# kopping_c.net
KiCad netlist of a schematic drawn in EAGLE
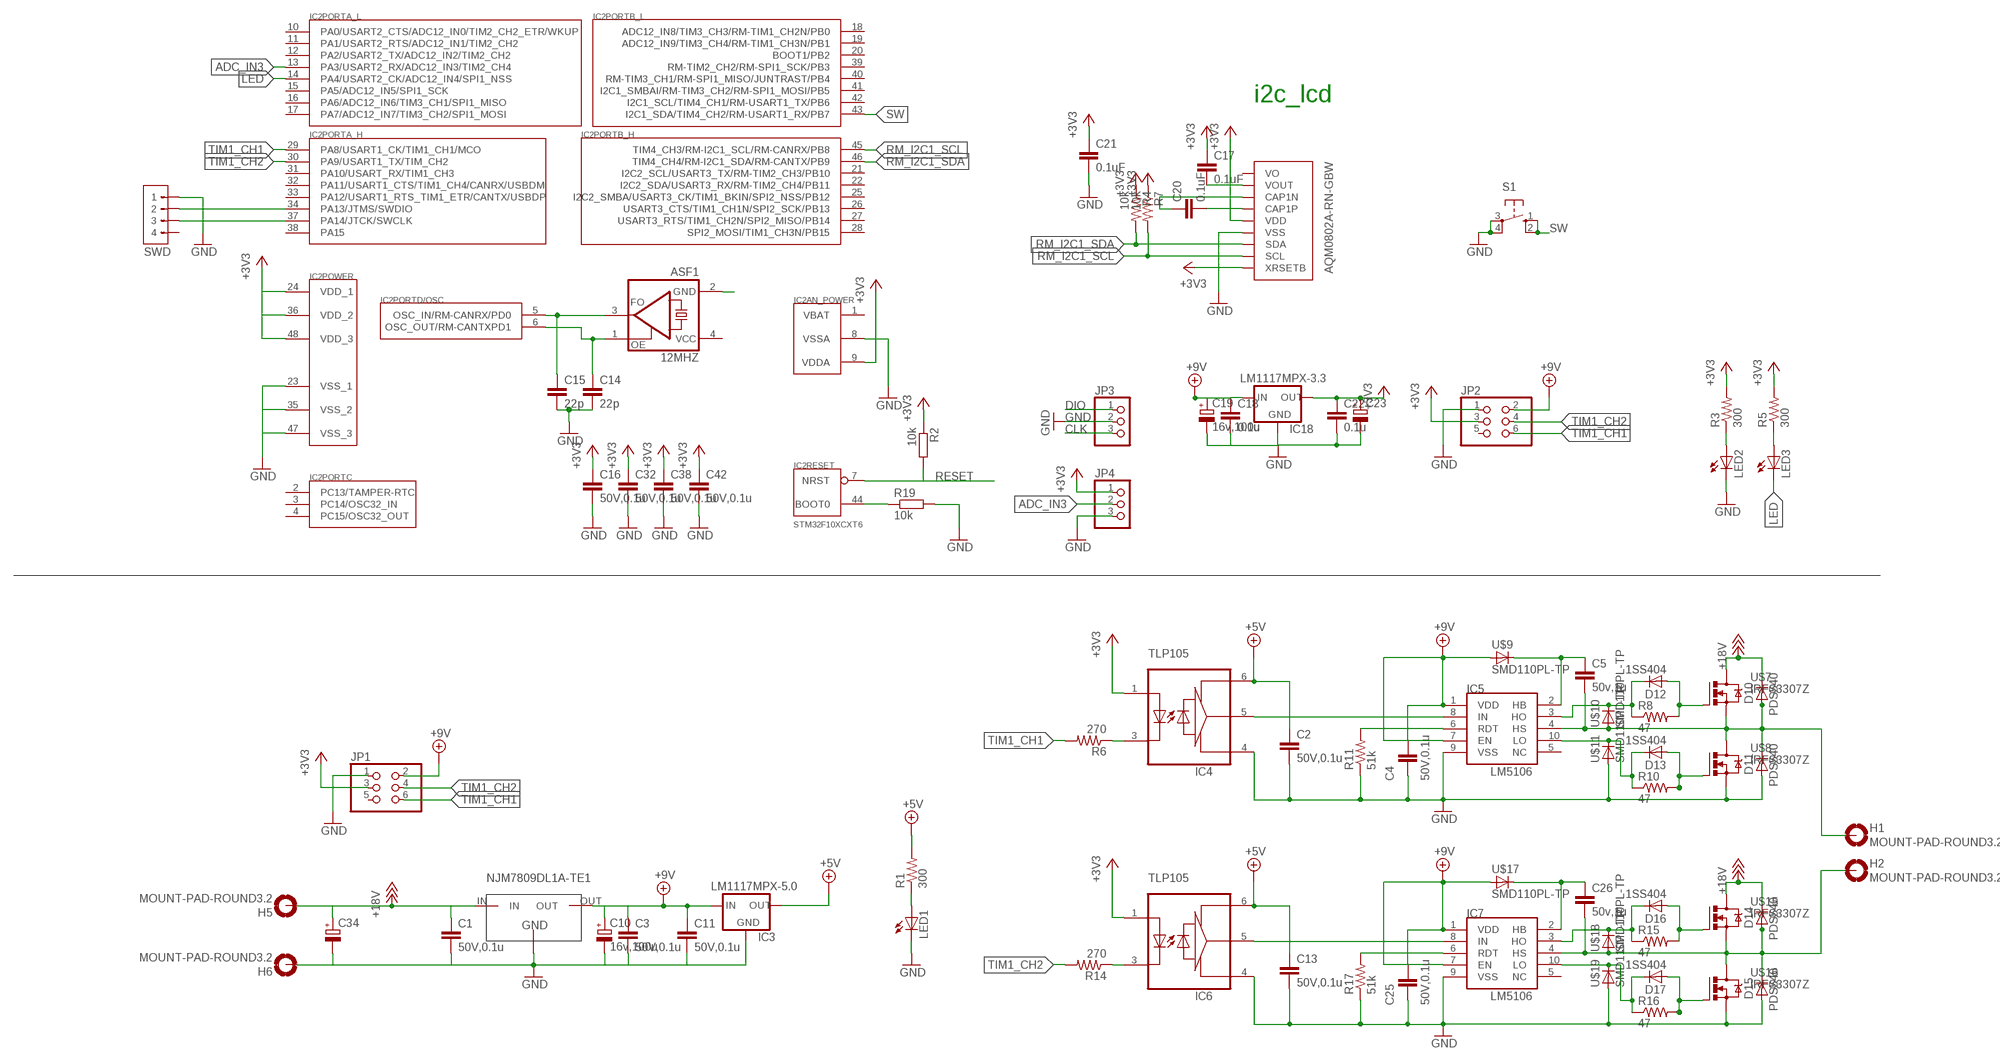
[diagram p0: schematic, sheet 1]

(export (version "E")
  (design (tool "Eeschema 10.0.6"))
  (components
    (comp (ref "12MHZ")
      (value "ASF1")
      (footprint "eagle-import:ASF")
      (libsource (lib "eagle-import") (part "ASF1"))
    )
    (comp (ref "AQM0802A-RN-GBW")
      (value "AQM0802A-RN-GBW")
      (footprint "eagle-import:AQM0802")
      (libsource (lib "eagle-import") (part "AQM0802A-RN-GBW"))
    )
    (comp (ref "C1")
      (value "50V,0.1u")
      (footprint "eagle-import:C0603")
      (libsource (lib "eagle-import") (part "C-EUC0603"))
    )
    (comp (ref "C2")
      (value "50V,0.1u")
      (footprint "eagle-import:C0603")
      (libsource (lib "eagle-import") (part "C-EUC0603"))
    )
    (comp (ref "C3")
      (value "50V,0.1u")
      (footprint "eagle-import:C0603")
      (libsource (lib "eagle-import") (part "C-EUC0603"))
    )
    (comp (ref "C4")
      (value "50V,0.1u")
      (footprint "eagle-import:C0603")
      (libsource (lib "eagle-import") (part "C-EUC0603"))
    )
    (comp (ref "C5")
      (value "50v,1u")
      (footprint "eagle-import:C0603")
      (libsource (lib "eagle-import") (part "C-EUC0603"))
    )
    (comp (ref "C10")
      (value "16v,100u")
      (footprint "eagle-import:153CLV-0605")
      (libsource (lib "eagle-import") (part "CPOL-EU153CLV-0605"))
    )
    (comp (ref "C11")
      (value "50V,0.1u")
      (footprint "eagle-import:C0603")
      (libsource (lib "eagle-import") (part "C-EUC0603"))
    )
    (comp (ref "C13")
      (value "50V,0.1u")
      (footprint "eagle-import:C0603")
      (libsource (lib "eagle-import") (part "C-EUC0603"))
    )
    (comp (ref "C14")
      (value "22p")
      (footprint "eagle-import:C0603")
      (libsource (lib "eagle-import") (part "C-EUC0603"))
    )
    (comp (ref "C15")
      (value "22p")
      (footprint "eagle-import:C0603")
      (libsource (lib "eagle-import") (part "C-EUC0603"))
    )
    (comp (ref "C16")
      (value "50V,0.1u")
      (footprint "eagle-import:C0603K")
      (libsource (lib "eagle-import") (part "resistor_C-EUC0603K"))
    )
    (comp (ref "C17")
      (value "0.1uF")
      (footprint "eagle-import:C0603")
      (libsource (lib "eagle-import") (part "resistor_C-EUC0603"))
    )
    (comp (ref "C18")
      (value "0.1u")
      (footprint "eagle-import:C0603")
      (libsource (lib "eagle-import") (part "C-EUC0603"))
    )
    (comp (ref "C19")
      (value "16v,100u")
      (footprint "eagle-import:153CLV-0605")
      (libsource (lib "eagle-import") (part "CPOL-EU153CLV-0605"))
    )
    (comp (ref "C20")
      (value "0.1uF")
      (footprint "eagle-import:C0603")
      (libsource (lib "eagle-import") (part "resistor_C-EUC0603"))
    )
    (comp (ref "C21")
      (value "0.1uF")
      (footprint "eagle-import:C0603")
      (libsource (lib "eagle-import") (part "resistor_C-EUC0603"))
    )
    (comp (ref "C22")
      (value "0.1u")
      (footprint "eagle-import:C0603K")
      (libsource (lib "eagle-import") (part "resistor_C-EUC0603K"))
    )
    (comp (ref "C23")
      (value "CPOL-EU153CLV-0505")
      (footprint "eagle-import:153CLV-0505")
      (libsource (lib "eagle-import") (part "CPOL-EU153CLV-0505"))
    )
    (comp (ref "C25")
      (value "50V,0.1u")
      (footprint "eagle-import:C0603")
      (libsource (lib "eagle-import") (part "C-EUC0603"))
    )
    (comp (ref "C26")
      (value "50v,1u")
      (footprint "eagle-import:C0603")
      (libsource (lib "eagle-import") (part "C-EUC0603"))
    )
    (comp (ref "C32")
      (value "50V,0.1u")
      (footprint "eagle-import:C0603K")
      (libsource (lib "eagle-import") (part "resistor_C-EUC0603K"))
    )
    (comp (ref "C34")
      (value "CPOL-EUE7.5-16")
      (footprint "eagle-import:E7,5-16")
      (libsource (lib "eagle-import") (part "CPOL-EUE7.5-16"))
    )
    (comp (ref "C38")
      (value "50V,0.1u")
      (footprint "eagle-import:C0603K")
      (libsource (lib "eagle-import") (part "resistor_C-EUC0603K"))
    )
    (comp (ref "C42")
      (value "50V,0.1u")
      (footprint "eagle-import:C0603K")
      (libsource (lib "eagle-import") (part "resistor_C-EUC0603K"))
    )
    (comp (ref "D10")
      (value "PDS540")
      (footprint "eagle-import:POWER_DI_5")
      (libsource (lib "eagle-import") (part "PDS540"))
    )
    (comp (ref "D11")
      (value "PDS540")
      (footprint "eagle-import:POWER_DI_5")
      (libsource (lib "eagle-import") (part "PDS540"))
    )
    (comp (ref "D12")
      (value "1SS404")
      (footprint "eagle-import:USC(1.25X2.5)")
      (libsource (lib "eagle-import") (part "1SS404"))
    )
    (comp (ref "D13")
      (value "1SS404")
      (footprint "eagle-import:USC(1.25X2.5)")
      (libsource (lib "eagle-import") (part "1SS404"))
    )
    (comp (ref "D14")
      (value "PDS540")
      (footprint "eagle-import:POWER_DI_5")
      (libsource (lib "eagle-import") (part "PDS540"))
    )
    (comp (ref "D15")
      (value "PDS540")
      (footprint "eagle-import:POWER_DI_5")
      (libsource (lib "eagle-import") (part "PDS540"))
    )
    (comp (ref "D16")
      (value "1SS404")
      (footprint "eagle-import:USC(1.25X2.5)")
      (libsource (lib "eagle-import") (part "1SS404"))
    )
    (comp (ref "D17")
      (value "1SS404")
      (footprint "eagle-import:USC(1.25X2.5)")
      (libsource (lib "eagle-import") (part "1SS404"))
    )
    (comp (ref "H1")
      (value "MOUNT-PAD-ROUND3.2")
      (footprint "eagle-import:3,2-PAD")
      (libsource (lib "eagle-import") (part "MOUNT-PAD-ROUND3.2"))
    )
    (comp (ref "H2")
      (value "MOUNT-PAD-ROUND3.2")
      (footprint "eagle-import:3,2-PAD")
      (libsource (lib "eagle-import") (part "MOUNT-PAD-ROUND3.2"))
    )
    (comp (ref "H5")
      (value "MOUNT-PAD-ROUND3.2")
      (footprint "eagle-import:3,2-PAD")
      (libsource (lib "eagle-import") (part "MOUNT-PAD-ROUND3.2"))
    )
    (comp (ref "H6")
      (value "MOUNT-PAD-ROUND3.2")
      (footprint "eagle-import:3,2-PAD")
      (libsource (lib "eagle-import") (part "MOUNT-PAD-ROUND3.2"))
    )
    (comp (ref "IC2")
      (value "STM32F10XCXT6")
      (footprint "eagle-import:TQFP48")
      (libsource (lib "eagle-import") (part "STM32F10XCXT6"))
    )
    (comp (ref "IC3")
      (value "LM1117MPX-5.0")
      (footprint "eagle-import:SOT223")
      (libsource (lib "eagle-import") (part "LM1117"))
    )
    (comp (ref "IC4")
      (value "TLP105")
      (footprint "eagle-import:MFSOP6")
      (libsource (lib "eagle-import") (part "TLP117"))
    )
    (comp (ref "IC5")
      (value "LM5106")
      (footprint "eagle-import:MSOP10")
      (libsource (lib "eagle-import") (part "LM5106"))
    )
    (comp (ref "IC6")
      (value "TLP105")
      (footprint "eagle-import:MFSOP6")
      (libsource (lib "eagle-import") (part "TLP117"))
    )
    (comp (ref "IC7")
      (value "LM5106")
      (footprint "eagle-import:MSOP10")
      (libsource (lib "eagle-import") (part "LM5106"))
    )
    (comp (ref "IC18")
      (value "LM1117MPX-3.3")
      (footprint "eagle-import:SOT223")
      (libsource (lib "eagle-import") (part "LM1117"))
    )
    (comp (ref "JP1")
      (value "PINHD-2X3")
      (footprint "eagle-import:2X03")
      (libsource (lib "eagle-import") (part "PINHD-2X3"))
    )
    (comp (ref "JP2")
      (value "PINHD-2X3")
      (footprint "eagle-import:2X03")
      (libsource (lib "eagle-import") (part "PINHD-2X3"))
    )
    (comp (ref "JP3")
      (value "PINHD-1X3/90")
      (footprint "eagle-import:1X03_90")
      (libsource (lib "eagle-import") (part "PINHD-1X3/90"))
    )
    (comp (ref "JP4")
      (value "PINHD-1X3/90")
      (footprint "eagle-import:1X03_90")
      (libsource (lib "eagle-import") (part "PINHD-1X3/90"))
    )
    (comp (ref "LED1")
      (value "LEDCHIPLED_1206")
      (footprint "eagle-import:CHIPLED_1206")
      (libsource (lib "eagle-import") (part "LEDCHIPLED_1206"))
    )
    (comp (ref "LED2")
      (value "LEDCHIPLED_1206")
      (footprint "eagle-import:CHIPLED_1206")
      (libsource (lib "eagle-import") (part "LEDCHIPLED_1206"))
    )
    (comp (ref "LED3")
      (value "LEDCHIPLED_1206")
      (footprint "eagle-import:CHIPLED_1206")
      (libsource (lib "eagle-import") (part "LEDCHIPLED_1206"))
    )
    (comp (ref "R1")
      (value "300")
      (footprint "eagle-import:M2012")
      (libsource (lib "eagle-import") (part "R-US_M2012"))
    )
    (comp (ref "R2")
      (value "10k")
      (footprint "eagle-import:R0603")
      (libsource (lib "eagle-import") (part "R-EU_R0603"))
    )
    (comp (ref "R3")
      (value "300")
      (footprint "eagle-import:M2012")
      (libsource (lib "eagle-import") (part "R-US_M2012"))
    )
    (comp (ref "R4")
      (value "10k")
      (footprint "eagle-import:R0603")
      (libsource (lib "eagle-import") (part "resistor_R-US_R0603"))
    )
    (comp (ref "R5")
      (value "300")
      (footprint "eagle-import:M2012")
      (libsource (lib "eagle-import") (part "R-US_M2012"))
    )
    (comp (ref "R6")
      (value "270")
      (footprint "eagle-import:R0603")
      (libsource (lib "eagle-import") (part "resistor_R-US_R0603"))
    )
    (comp (ref "R7")
      (value "10k")
      (footprint "eagle-import:R0603")
      (libsource (lib "eagle-import") (part "resistor_R-US_R0603"))
    )
    (comp (ref "R8")
      (value "47")
      (footprint "eagle-import:R0603")
      (libsource (lib "eagle-import") (part "resistor_R-US_R0603"))
    )
    (comp (ref "R10")
      (value "47")
      (footprint "eagle-import:R0603")
      (libsource (lib "eagle-import") (part "resistor_R-US_R0603"))
    )
    (comp (ref "R11")
      (value "51k")
      (footprint "eagle-import:R0603")
      (libsource (lib "eagle-import") (part "R-US_R0603"))
    )
    (comp (ref "R14")
      (value "270")
      (footprint "eagle-import:R0603")
      (libsource (lib "eagle-import") (part "resistor_R-US_R0603"))
    )
    (comp (ref "R15")
      (value "47")
      (footprint "eagle-import:R0603")
      (libsource (lib "eagle-import") (part "resistor_R-US_R0603"))
    )
    (comp (ref "R16")
      (value "47")
      (footprint "eagle-import:R0603")
      (libsource (lib "eagle-import") (part "resistor_R-US_R0603"))
    )
    (comp (ref "R17")
      (value "51k")
      (footprint "eagle-import:R0603")
      (libsource (lib "eagle-import") (part "R-US_R0603"))
    )
    (comp (ref "R19")
      (value "10k")
      (footprint "eagle-import:R0603")
      (libsource (lib "eagle-import") (part "R-EU_R0603"))
    )
    (comp (ref "S1")
      (value "10-XX")
      (footprint "eagle-import:B3F-10XX")
      (fields (field (name "MPN") "B3F-1000"))
      (libsource (lib "eagle-import") (part "10-XX"))
    )
    (comp (ref "SWD")
      (value "TOP_TYPE_4PIN")
      (footprint "eagle-import:TOP_TYPE_4PIN")
      (libsource (lib "eagle-import") (part "TOP_TYPE_4PIN"))
    )
    (comp (ref "U$3")
      (value "TO252")
      (footprint "eagle-import:TO252")
      (libsource (lib "eagle-import") (part "TO252"))
    )
    (comp (ref "U$7")
      (value "IRFS3307Z")
      (footprint "eagle-import:IRFS3307Z")
      (libsource (lib "eagle-import") (part "IRFS3307Z"))
    )
    (comp (ref "U$8")
      (value "IRFS3307Z")
      (footprint "eagle-import:IRFS3307Z")
      (libsource (lib "eagle-import") (part "IRFS3307Z"))
    )
    (comp (ref "U$9")
      (value "SMD110PL-TP")
      (footprint "eagle-import:SOD123")
      (libsource (lib "eagle-import") (part "SMD110PL-TP"))
    )
    (comp (ref "U$10")
      (value "SMD110PL-TP")
      (footprint "eagle-import:SOD123")
      (libsource (lib "eagle-import") (part "SMD110PL-TP"))
    )
    (comp (ref "U$11")
      (value "SMD110PL-TP")
      (footprint "eagle-import:SOD123")
      (libsource (lib "eagle-import") (part "SMD110PL-TP"))
    )
    (comp (ref "U$15")
      (value "IRFS3307Z")
      (footprint "eagle-import:IRFS3307Z")
      (libsource (lib "eagle-import") (part "IRFS3307Z"))
    )
    (comp (ref "U$16")
      (value "IRFS3307Z")
      (footprint "eagle-import:IRFS3307Z")
      (libsource (lib "eagle-import") (part "IRFS3307Z"))
    )
    (comp (ref "U$17")
      (value "SMD110PL-TP")
      (footprint "eagle-import:SOD123")
      (libsource (lib "eagle-import") (part "SMD110PL-TP"))
    )
    (comp (ref "U$18")
      (value "SMD110PL-TP")
      (footprint "eagle-import:SOD123")
      (libsource (lib "eagle-import") (part "SMD110PL-TP"))
    )
    (comp (ref "U$19")
      (value "SMD110PL-TP")
      (footprint "eagle-import:SOD123")
      (libsource (lib "eagle-import") (part "SMD110PL-TP"))
    )
  )
  (nets
    (net (code "1") (name "+3V3") (class "Default")
      (node (ref "AQM0802A-RN-GBW") (pin "P$5") (pinfunction "VDD_P$5") (pintype "bidirectional"))
      (node (ref "AQM0802A-RN-GBW") (pin "P$9") (pinfunction "XRSETB_P$9") (pintype "bidirectional"))
      (node (ref "C16") (pin "1") (pinfunction "1_1") (pintype "passive"))
      (node (ref "C17") (pin "1") (pinfunction "1_1") (pintype "passive"))
      (node (ref "C21") (pin "1") (pinfunction "1_1") (pintype "passive"))
      (node (ref "C22") (pin "1") (pinfunction "1_1") (pintype "passive"))
      (node (ref "C23") (pin "+") (pinfunction "+_+") (pintype "passive"))
      (node (ref "C32") (pin "1") (pinfunction "1_1") (pintype "passive"))
      (node (ref "C38") (pin "1") (pinfunction "1_1") (pintype "passive"))
      (node (ref "C42") (pin "1") (pinfunction "1_1") (pintype "passive"))
      (node (ref "IC18") (pin "2") (pinfunction "OUT1_2") (pintype "passive"))
      (node (ref "IC18") (pin "4") (pinfunction "OUT_4") (pintype "passive"))
      (node (ref "IC2") (pin "24") (pinfunction "VDD_1_24") (pintype "power_in"))
      (node (ref "IC2") (pin "36") (pinfunction "VDD_2_36") (pintype "power_in"))
      (node (ref "IC2") (pin "48") (pinfunction "VDD_3_48") (pintype "power_in"))
      (node (ref "IC2") (pin "9") (pinfunction "VDDA_9") (pintype "power_in"))
      (node (ref "IC4") (pin "1") (pinfunction "1_1") (pintype "input"))
      (node (ref "IC6") (pin "1") (pinfunction "1_1") (pintype "input"))
      (node (ref "JP1") (pin "3") (pinfunction "3_3") (pintype "passive"))
      (node (ref "JP2") (pin "3") (pinfunction "3_3") (pintype "passive"))
      (node (ref "JP4") (pin "1") (pinfunction "1_1") (pintype "passive"))
      (node (ref "R2") (pin "1") (pinfunction "1_1") (pintype "passive"))
      (node (ref "R3") (pin "2") (pinfunction "2_2") (pintype "passive"))
      (node (ref "R4") (pin "1") (pinfunction "1_1") (pintype "passive"))
      (node (ref "R5") (pin "2") (pinfunction "2_2") (pintype "passive"))
      (node (ref "R7") (pin "1") (pinfunction "1_1") (pintype "passive"))
    )
    (net (code "2") (name "+5V") (class "Default")
      (node (ref "C13") (pin "1") (pinfunction "1_1") (pintype "passive"))
      (node (ref "C2") (pin "1") (pinfunction "1_1") (pintype "passive"))
      (node (ref "IC3") (pin "2") (pinfunction "OUT1_2") (pintype "passive"))
      (node (ref "IC3") (pin "4") (pinfunction "OUT_4") (pintype "passive"))
      (node (ref "IC4") (pin "6") (pinfunction "VCC_6") (pintype "power_in"))
      (node (ref "IC6") (pin "6") (pinfunction "VCC_6") (pintype "power_in"))
      (node (ref "R1") (pin "2") (pinfunction "2_2") (pintype "passive"))
    )
    (net (code "3") (name "+9V") (class "Default")
      (node (ref "C10") (pin "+") (pinfunction "+_+") (pintype "passive"))
      (node (ref "C11") (pin "1") (pinfunction "1_1") (pintype "passive"))
      (node (ref "C18") (pin "1") (pinfunction "1_1") (pintype "passive"))
      (node (ref "C19") (pin "+") (pinfunction "+_+") (pintype "passive"))
      (node (ref "C25") (pin "1") (pinfunction "1_1") (pintype "passive"))
      (node (ref "C3") (pin "1") (pinfunction "1_1") (pintype "passive"))
      (node (ref "C4") (pin "1") (pinfunction "1_1") (pintype "passive"))
      (node (ref "IC18") (pin "3") (pinfunction "IN_3") (pintype "input"))
      (node (ref "IC3") (pin "3") (pinfunction "IN_3") (pintype "input"))
      (node (ref "IC5") (pin "1") (pinfunction "VDD_1") (pintype "power_in"))
      (node (ref "IC5") (pin "7") (pinfunction "EN_7") (pintype "input"))
      (node (ref "IC7") (pin "1") (pinfunction "VDD_1") (pintype "power_in"))
      (node (ref "IC7") (pin "7") (pinfunction "EN_7") (pintype "input"))
      (node (ref "JP1") (pin "2") (pinfunction "2_2") (pintype "passive"))
      (node (ref "JP2") (pin "2") (pinfunction "2_2") (pintype "passive"))
      (node (ref "U$17") (pin "A") (pinfunction "A_A") (pintype "passive"))
      (node (ref "U$3") (pin "OUT") (pinfunction "OUT_OUT") (pintype "bidirectional"))
      (node (ref "U$9") (pin "A") (pinfunction "A_A") (pintype "passive"))
    )
    (net (code "4") (name "+18V") (class "Default")
      (node (ref "C1") (pin "1") (pinfunction "1_1") (pintype "passive"))
      (node (ref "C34") (pin "+") (pinfunction "+_+") (pintype "passive"))
      (node (ref "D10") (pin "K") (pinfunction "C_K") (pintype "passive"))
      (node (ref "D14") (pin "K") (pinfunction "C_K") (pintype "passive"))
      (node (ref "H5") (pin "B3,2") (pinfunction "MOUNT_B3,2") (pintype "passive"))
      (node (ref "U$15") (pin "2") (pinfunction "D1_2") (pintype "passive"))
      (node (ref "U$3") (pin "IN") (pinfunction "IN_IN") (pintype "bidirectional"))
      (node (ref "U$7") (pin "2") (pinfunction "D1_2") (pintype "passive"))
    )
    (net (code "5") (name "/CLK") (class "Default")
      (node (ref "IC2") (pin "37") (pinfunction "PA14/JTCK/SWCLK_37") (pintype "bidirectional"))
      (node (ref "JP3") (pin "3") (pinfunction "3_3") (pintype "passive"))
      (node (ref "SWD") (pin "3") (pinfunction "3_3") (pintype "passive"))
    )
    (net (code "6") (name "/DIO") (class "Default")
      (node (ref "IC2") (pin "34") (pinfunction "PA13/JTMS/SWDIO_34") (pintype "bidirectional"))
      (node (ref "JP3") (pin "1") (pinfunction "1_1") (pintype "passive"))
      (node (ref "SWD") (pin "2") (pinfunction "2_2") (pintype "passive"))
    )
    (net (code "7") (name "/RESET") (class "Default")
      (node (ref "IC2") (pin "7") (pinfunction "NRST_7") (pintype "input"))
      (node (ref "R2") (pin "2") (pinfunction "2_2") (pintype "passive"))
    )
    (net (code "8") (name "/VBAT") (class "Default")
      (node (ref "IC2") (pin "1") (pinfunction "VBAT_1") (pintype "power_in"))
    )
    (net (code "9") (name "/VCC") (class "Default")
      (node (ref "12MHZ") (pin "4") (pinfunction "VCC_4") (pintype "power_in"))
    )
    (net (code "10") (name "ADC_IN3") (class "Default")
      (node (ref "IC2") (pin "13") (pinfunction "PA3/USART2_RX/ADC12_IN3/TIM2_CH4_13") (pintype "bidirectional"))
      (node (ref "JP4") (pin "2") (pinfunction "2_2") (pintype "passive"))
    )
    (net (code "11") (name "GND") (class "Default")
      (node (ref "AQM0802A-RN-GBW") (pin "P$6") (pinfunction "VSS_P$6") (pintype "bidirectional"))
      (node (ref "C1") (pin "2") (pinfunction "2_2") (pintype "passive"))
      (node (ref "C10") (pin "-") (pinfunction "-_-") (pintype "passive"))
      (node (ref "C11") (pin "2") (pinfunction "2_2") (pintype "passive"))
      (node (ref "C13") (pin "2") (pinfunction "2_2") (pintype "passive"))
      (node (ref "C14") (pin "2") (pinfunction "2_2") (pintype "passive"))
      (node (ref "C15") (pin "2") (pinfunction "2_2") (pintype "passive"))
      (node (ref "C16") (pin "2") (pinfunction "2_2") (pintype "passive"))
      (node (ref "C18") (pin "2") (pinfunction "2_2") (pintype "passive"))
      (node (ref "C19") (pin "-") (pinfunction "-_-") (pintype "passive"))
      (node (ref "C2") (pin "2") (pinfunction "2_2") (pintype "passive"))
      (node (ref "C21") (pin "2") (pinfunction "2_2") (pintype "passive"))
      (node (ref "C22") (pin "2") (pinfunction "2_2") (pintype "passive"))
      (node (ref "C23") (pin "-") (pinfunction "-_-") (pintype "passive"))
      (node (ref "C25") (pin "2") (pinfunction "2_2") (pintype "passive"))
      (node (ref "C3") (pin "2") (pinfunction "2_2") (pintype "passive"))
      (node (ref "C32") (pin "2") (pinfunction "2_2") (pintype "passive"))
      (node (ref "C34") (pin "-") (pinfunction "-_-") (pintype "passive"))
      (node (ref "C38") (pin "2") (pinfunction "2_2") (pintype "passive"))
      (node (ref "C4") (pin "2") (pinfunction "2_2") (pintype "passive"))
      (node (ref "C42") (pin "2") (pinfunction "2_2") (pintype "passive"))
      (node (ref "D11") (pin "A1") (pinfunction "A1_A1") (pintype "passive"))
      (node (ref "D11") (pin "A2") (pinfunction "A_A2") (pintype "passive"))
      (node (ref "D15") (pin "A1") (pinfunction "A1_A1") (pintype "passive"))
      (node (ref "D15") (pin "A2") (pinfunction "A_A2") (pintype "passive"))
      (node (ref "H6") (pin "B3,2") (pinfunction "MOUNT_B3,2") (pintype "passive"))
      (node (ref "IC18") (pin "1") (pinfunction "GND_1") (pintype "input"))
      (node (ref "IC2") (pin "23") (pinfunction "VSS_1_23") (pintype "power_in"))
      (node (ref "IC2") (pin "35") (pinfunction "VSS_2_35") (pintype "power_in"))
      (node (ref "IC2") (pin "47") (pinfunction "VSS_3_47") (pintype "power_in"))
      (node (ref "IC2") (pin "8") (pinfunction "VSSA_8") (pintype "power_in"))
      (node (ref "IC3") (pin "1") (pinfunction "GND_1") (pintype "input"))
      (node (ref "IC4") (pin "4") (pinfunction "GND_4") (pintype "power_in"))
      (node (ref "IC5") (pin "9") (pinfunction "VSS_9") (pintype "power_in"))
      (node (ref "IC6") (pin "4") (pinfunction "GND_4") (pintype "power_in"))
      (node (ref "IC7") (pin "9") (pinfunction "VSS_9") (pintype "power_in"))
      (node (ref "JP1") (pin "1") (pinfunction "1_1") (pintype "passive"))
      (node (ref "JP2") (pin "1") (pinfunction "1_1") (pintype "passive"))
      (node (ref "JP3") (pin "2") (pinfunction "2_2") (pintype "passive"))
      (node (ref "JP4") (pin "3") (pinfunction "3_3") (pintype "passive"))
      (node (ref "LED1") (pin "C") (pinfunction "C_C") (pintype "passive"))
      (node (ref "LED2") (pin "C") (pinfunction "C_C") (pintype "passive"))
      (node (ref "R11") (pin "1") (pinfunction "1_1") (pintype "passive"))
      (node (ref "R17") (pin "1") (pinfunction "1_1") (pintype "passive"))
      (node (ref "R19") (pin "2") (pinfunction "2_2") (pintype "passive"))
      (node (ref "S1") (pin "3") (pinfunction "P_3") (pintype "passive"))
      (node (ref "S1") (pin "4") (pinfunction "P1_4") (pintype "passive"))
      (node (ref "SWD") (pin "1") (pinfunction "1_1") (pintype "passive"))
      (node (ref "U$11") (pin "A") (pinfunction "A_A") (pintype "passive"))
      (node (ref "U$16") (pin "3") (pinfunction "S_3") (pintype "passive"))
      (node (ref "U$19") (pin "A") (pinfunction "A_A") (pintype "passive"))
      (node (ref "U$3") (pin "GND") (pinfunction "GND_GND") (pintype "bidirectional"))
      (node (ref "U$8") (pin "3") (pinfunction "S_3") (pintype "passive"))
    )
    (net (code "12") (name "LED") (class "Default")
      (node (ref "IC2") (pin "14") (pinfunction "PA4/USART2_CK/ADC12_IN4/SPI1_NSS_14") (pintype "bidirectional"))
      (node (ref "LED3") (pin "C") (pinfunction "C_C") (pintype "passive"))
    )
    (net (code "13") (name "Net-(12MHZ-FO)") (class "Default")
      (node (ref "12MHZ") (pin "3") (pinfunction "FO_3") (pintype "output"))
      (node (ref "C15") (pin "1") (pinfunction "1_1") (pintype "passive"))
      (node (ref "IC2") (pin "5") (pinfunction "OSC_IN/RM-CANRX/PD0_5") (pintype "bidirectional"))
    )
    (net (code "14") (name "Net-(12MHZ-OE)") (class "Default")
      (node (ref "12MHZ") (pin "1") (pinfunction "OE_1") (pintype "input"))
      (node (ref "C14") (pin "1") (pinfunction "1_1") (pintype "passive"))
      (node (ref "IC2") (pin "6") (pinfunction "OSC_OUT/RM-CANTXPD1_6") (pintype "bidirectional"))
    )
    (net (code "15") (name "Net-(AQM0802A-RN-GBW-CAP1N)") (class "Default")
      (node (ref "AQM0802A-RN-GBW") (pin "P$3") (pinfunction "CAP1N_P$3") (pintype "bidirectional"))
      (node (ref "C20") (pin "1") (pinfunction "1_1") (pintype "passive"))
    )
    (net (code "16") (name "Net-(AQM0802A-RN-GBW-CAP1P)") (class "Default")
      (node (ref "AQM0802A-RN-GBW") (pin "P$4") (pinfunction "CAP1P_P$4") (pintype "bidirectional"))
      (node (ref "C20") (pin "2") (pinfunction "2_2") (pintype "passive"))
    )
    (net (code "17") (name "Net-(AQM0802A-RN-GBW-VOUT)") (class "Default")
      (node (ref "AQM0802A-RN-GBW") (pin "P$2") (pinfunction "VOUT_P$2") (pintype "bidirectional"))
      (node (ref "C17") (pin "2") (pinfunction "2_2") (pintype "passive"))
    )
    (net (code "18") (name "Net-(D10-A)") (class "Default")
      (node (ref "C5") (pin "2") (pinfunction "2_2") (pintype "passive"))
      (node (ref "D10") (pin "A1") (pinfunction "A1_A1") (pintype "passive"))
      (node (ref "D10") (pin "A2") (pinfunction "A_A2") (pintype "passive"))
      (node (ref "D11") (pin "K") (pinfunction "C_K") (pintype "passive"))
      (node (ref "H1") (pin "B3,2") (pinfunction "MOUNT_B3,2") (pintype "passive"))
      (node (ref "IC5") (pin "4") (pinfunction "HS_4") (pintype "passive"))
      (node (ref "U$10") (pin "A") (pinfunction "A_A") (pintype "passive"))
      (node (ref "U$7") (pin "3") (pinfunction "S_3") (pintype "passive"))
      (node (ref "U$8") (pin "2") (pinfunction "D1_2") (pintype "passive"))
    )
    (net (code "19") (name "Net-(D12-C)") (class "Default")
      (node (ref "D12") (pin "K") (pinfunction "C_K") (pintype "passive"))
      (node (ref "IC5") (pin "3") (pinfunction "HO_3") (pintype "output"))
      (node (ref "R8") (pin "1") (pinfunction "1_1") (pintype "passive"))
      (node (ref "U$10") (pin "K") (pinfunction "C_K") (pintype "passive"))
    )
    (net (code "20") (name "Net-(D13-C)") (class "Default")
      (node (ref "D13") (pin "K") (pinfunction "C_K") (pintype "passive"))
      (node (ref "IC5") (pin "10") (pinfunction "LO_10") (pintype "output"))
      (node (ref "R10") (pin "1") (pinfunction "1_1") (pintype "passive"))
      (node (ref "U$11") (pin "K") (pinfunction "C_K") (pintype "passive"))
    )
    (net (code "21") (name "Net-(D14-A)") (class "Default")
      (node (ref "C26") (pin "2") (pinfunction "2_2") (pintype "passive"))
      (node (ref "D14") (pin "A1") (pinfunction "A1_A1") (pintype "passive"))
      (node (ref "D14") (pin "A2") (pinfunction "A_A2") (pintype "passive"))
      (node (ref "D15") (pin "K") (pinfunction "C_K") (pintype "passive"))
      (node (ref "H2") (pin "B3,2") (pinfunction "MOUNT_B3,2") (pintype "passive"))
      (node (ref "IC7") (pin "4") (pinfunction "HS_4") (pintype "passive"))
      (node (ref "U$15") (pin "3") (pinfunction "S_3") (pintype "passive"))
      (node (ref "U$16") (pin "2") (pinfunction "D1_2") (pintype "passive"))
      (node (ref "U$18") (pin "A") (pinfunction "A_A") (pintype "passive"))
    )
    (net (code "22") (name "Net-(D16-C)") (class "Default")
      (node (ref "D16") (pin "K") (pinfunction "C_K") (pintype "passive"))
      (node (ref "IC7") (pin "3") (pinfunction "HO_3") (pintype "output"))
      (node (ref "R15") (pin "1") (pinfunction "1_1") (pintype "passive"))
      (node (ref "U$18") (pin "K") (pinfunction "C_K") (pintype "passive"))
    )
    (net (code "23") (name "Net-(D17-C)") (class "Default")
      (node (ref "D17") (pin "K") (pinfunction "C_K") (pintype "passive"))
      (node (ref "IC7") (pin "10") (pinfunction "LO_10") (pintype "output"))
      (node (ref "R16") (pin "1") (pinfunction "1_1") (pintype "passive"))
      (node (ref "U$19") (pin "K") (pinfunction "C_K") (pintype "passive"))
    )
    (net (code "24") (name "Net-(IC2I-BOOT0)") (class "Default")
      (node (ref "IC2") (pin "44") (pinfunction "BOOT0_44") (pintype "input"))
      (node (ref "R19") (pin "1") (pinfunction "1_1") (pintype "passive"))
    )
    (net (code "25") (name "Net-(IC4-Pad3)") (class "Default")
      (node (ref "IC4") (pin "3") (pinfunction "3_3") (pintype "output"))
      (node (ref "R6") (pin "1") (pinfunction "1_1") (pintype "passive"))
    )
    (net (code "26") (name "Net-(IC5-HB)") (class "Default")
      (node (ref "C5") (pin "1") (pinfunction "1_1") (pintype "passive"))
      (node (ref "IC5") (pin "2") (pinfunction "HB_2") (pintype "passive"))
      (node (ref "U$9") (pin "K") (pinfunction "C_K") (pintype "passive"))
    )
    (net (code "27") (name "Net-(IC5-IN)") (class "Default")
      (node (ref "IC4") (pin "5") (pinfunction "5_5") (pintype "output"))
      (node (ref "IC5") (pin "8") (pinfunction "IN_8") (pintype "input"))
    )
    (net (code "28") (name "Net-(IC5-RDT)") (class "Default")
      (node (ref "IC5") (pin "6") (pinfunction "RDT_6") (pintype "passive"))
      (node (ref "R11") (pin "2") (pinfunction "2_2") (pintype "passive"))
    )
    (net (code "29") (name "Net-(IC6-Pad3)") (class "Default")
      (node (ref "IC6") (pin "3") (pinfunction "3_3") (pintype "output"))
      (node (ref "R14") (pin "1") (pinfunction "1_1") (pintype "passive"))
    )
    (net (code "30") (name "Net-(IC7-HB)") (class "Default")
      (node (ref "C26") (pin "1") (pinfunction "1_1") (pintype "passive"))
      (node (ref "IC7") (pin "2") (pinfunction "HB_2") (pintype "passive"))
      (node (ref "U$17") (pin "K") (pinfunction "C_K") (pintype "passive"))
    )
    (net (code "31") (name "Net-(IC7-IN)") (class "Default")
      (node (ref "IC6") (pin "5") (pinfunction "5_5") (pintype "output"))
      (node (ref "IC7") (pin "8") (pinfunction "IN_8") (pintype "input"))
    )
    (net (code "32") (name "Net-(IC7-RDT)") (class "Default")
      (node (ref "IC7") (pin "6") (pinfunction "RDT_6") (pintype "passive"))
      (node (ref "R17") (pin "2") (pinfunction "2_2") (pintype "passive"))
    )
    (net (code "33") (name "Net-(LED1-PadA)") (class "Default")
      (node (ref "LED1") (pin "A") (pinfunction "A_A") (pintype "passive"))
      (node (ref "R1") (pin "1") (pinfunction "1_1") (pintype "passive"))
    )
    (net (code "34") (name "Net-(LED2-PadA)") (class "Default")
      (node (ref "LED2") (pin "A") (pinfunction "A_A") (pintype "passive"))
      (node (ref "R3") (pin "1") (pinfunction "1_1") (pintype "passive"))
    )
    (net (code "35") (name "Net-(LED3-PadA)") (class "Default")
      (node (ref "LED3") (pin "A") (pinfunction "A_A") (pintype "passive"))
      (node (ref "R5") (pin "1") (pinfunction "1_1") (pintype "passive"))
    )
    (net (code "36") (name "Net-(U$7-G1)") (class "Default")
      (node (ref "D12") (pin "A") (pinfunction "A_A") (pintype "passive"))
      (node (ref "R8") (pin "2") (pinfunction "2_2") (pintype "passive"))
      (node (ref "U$7") (pin "1") (pinfunction "G1_1") (pintype "passive"))
    )
    (net (code "37") (name "Net-(U$8-G1)") (class "Default")
      (node (ref "D13") (pin "A") (pinfunction "A_A") (pintype "passive"))
      (node (ref "R10") (pin "2") (pinfunction "2_2") (pintype "passive"))
      (node (ref "U$8") (pin "1") (pinfunction "G1_1") (pintype "passive"))
    )
    (net (code "38") (name "Net-(U$15-G1)") (class "Default")
      (node (ref "D16") (pin "A") (pinfunction "A_A") (pintype "passive"))
      (node (ref "R15") (pin "2") (pinfunction "2_2") (pintype "passive"))
      (node (ref "U$15") (pin "1") (pinfunction "G1_1") (pintype "passive"))
    )
    (net (code "39") (name "Net-(U$16-G1)") (class "Default")
      (node (ref "D17") (pin "A") (pinfunction "A_A") (pintype "passive"))
      (node (ref "R16") (pin "2") (pinfunction "2_2") (pintype "passive"))
      (node (ref "U$16") (pin "1") (pinfunction "G1_1") (pintype "passive"))
    )
    (net (code "40") (name "RM_I2C1_SCL") (class "Default")
      (node (ref "AQM0802A-RN-GBW") (pin "P$8") (pinfunction "SCL_P$8") (pintype "bidirectional"))
      (node (ref "IC2") (pin "45") (pinfunction "TIM4_CH3/RM-I2C1_SCL/RM-CANRX/PB8_45") (pintype "bidirectional"))
      (node (ref "R7") (pin "2") (pinfunction "2_2") (pintype "passive"))
    )
    (net (code "41") (name "RM_I2C1_SDA") (class "Default")
      (node (ref "AQM0802A-RN-GBW") (pin "P$7") (pinfunction "SDA_P$7") (pintype "bidirectional"))
      (node (ref "IC2") (pin "46") (pinfunction "TIM4_CH4/RM-I2C1_SDA/RM-CANTX/PB9_46") (pintype "bidirectional"))
      (node (ref "R4") (pin "2") (pinfunction "2_2") (pintype "passive"))
    )
    (net (code "42") (name "SW") (class "Default")
      (node (ref "IC2") (pin "43") (pinfunction "I2C1_SDA/TIM4_CH2/RM-USART1_RX/PB7_43") (pintype "bidirectional"))
      (node (ref "S1") (pin "1") (pinfunction "S_1") (pintype "passive"))
      (node (ref "S1") (pin "2") (pinfunction "S1_2") (pintype "passive"))
    )
    (net (code "43") (name "TIM1_CH1") (class "Default")
      (node (ref "IC2") (pin "29") (pinfunction "PA8/USART1_CK/TIM1_CH1/MCO_29") (pintype "bidirectional"))
      (node (ref "JP1") (pin "6") (pinfunction "6_6") (pintype "passive"))
      (node (ref "JP2") (pin "6") (pinfunction "6_6") (pintype "passive"))
      (node (ref "R6") (pin "2") (pinfunction "2_2") (pintype "passive"))
    )
    (net (code "44") (name "TIM1_CH2") (class "Default")
      (node (ref "IC2") (pin "30") (pinfunction "PA9/USART1_TX/TIM_CH2_30") (pintype "bidirectional"))
      (node (ref "JP1") (pin "4") (pinfunction "4_4") (pintype "passive"))
      (node (ref "JP2") (pin "4") (pinfunction "4_4") (pintype "passive"))
      (node (ref "R14") (pin "2") (pinfunction "2_2") (pintype "passive"))
    )
    (net (code "45") (name "unconnected-(12MHZ-GND-Pad2)") (class "Default")
      (node (ref "12MHZ") (pin "2") (pinfunction "GND_2") (pintype "power_in"))
    )
    (net (code "46") (name "unconnected-(AQM0802A-RN-GBW-VO-PadP$1)") (class "Default")
      (node (ref "AQM0802A-RN-GBW") (pin "P$1") (pinfunction "VO_P$1") (pintype "bidirectional"))
    )
    (net (code "47") (name "unconnected-(IC2B-PA10{slash}USART_RX{slash}TIM1_CH3-Pad31)") (class "Default")
      (node (ref "IC2") (pin "31") (pinfunction "PA10/USART_RX/TIM1_CH3_31") (pintype "bidirectional"))
    )
    (net (code "48") (name "unconnected-(IC2B-PA11{slash}USART1_CTS{slash}TIM1_CH4{slash}CANRX{slash}USBDM-Pad32)") (class "Default")
      (node (ref "IC2") (pin "32") (pinfunction "PA11/USART1_CTS/TIM1_CH4/CANRX/USBDM_32") (pintype "bidirectional"))
    )
    (net (code "49") (name "unconnected-(IC2B-PA12{slash}USART1_RTS_TIM1_ETR{slash}CANTX{slash}USBDP-Pad33)") (class "Default")
      (node (ref "IC2") (pin "33") (pinfunction "PA12/USART1_RTS_TIM1_ETR/CANTX/USBDP_33") (pintype "bidirectional"))
    )
    (net (code "50") (name "unconnected-(IC2B-PA15-Pad38)") (class "Default")
      (node (ref "IC2") (pin "38") (pinfunction "PA15_38") (pintype "bidirectional"))
    )
    (net (code "51") (name "unconnected-(IC2C-PA0{slash}USART2_CTS{slash}ADC12_IN0{slash}TIM2_CH2_ETR{slash}WKUP-Pad10)") (class "Default")
      (node (ref "IC2") (pin "10") (pinfunction "PA0/USART2_CTS/ADC12_IN0/TIM2_CH2_ETR/WKUP_10") (pintype "bidirectional"))
    )
    (net (code "52") (name "unconnected-(IC2C-PA1{slash}USART2_RTS{slash}ADC12_IN1{slash}TIM2_CH2-Pad11)") (class "Default")
      (node (ref "IC2") (pin "11") (pinfunction "PA1/USART2_RTS/ADC12_IN1/TIM2_CH2_11") (pintype "bidirectional"))
    )
    (net (code "53") (name "unconnected-(IC2C-PA2{slash}USART2_TX{slash}ADC12_IN2{slash}TIM2_CH2-Pad12)") (class "Default")
      (node (ref "IC2") (pin "12") (pinfunction "PA2/USART2_TX/ADC12_IN2/TIM2_CH2_12") (pintype "bidirectional"))
    )
    (net (code "54") (name "unconnected-(IC2C-PA5{slash}ADC12_IN5{slash}SPI1_SCK-Pad15)") (class "Default")
      (node (ref "IC2") (pin "15") (pinfunction "PA5/ADC12_IN5/SPI1_SCK_15") (pintype "bidirectional"))
    )
    (net (code "55") (name "unconnected-(IC2C-PA6{slash}ADC12_IN6{slash}TIM3_CH1{slash}SPI1_MISO-Pad16)") (class "Default")
      (node (ref "IC2") (pin "16") (pinfunction "PA6/ADC12_IN6/TIM3_CH1/SPI1_MISO_16") (pintype "bidirectional"))
    )
    (net (code "56") (name "unconnected-(IC2C-PA7{slash}ADC12_IN7{slash}TIM3_CH2{slash}SPI1_MOSI-Pad17)") (class "Default")
      (node (ref "IC2") (pin "17") (pinfunction "PA7/ADC12_IN7/TIM3_CH2/SPI1_MOSI_17") (pintype "bidirectional"))
    )
    (net (code "57") (name "unconnected-(IC2D-I2C2_SCL{slash}USART3_TX{slash}RM-TIM2_CH3{slash}PB10-Pad21)") (class "Default")
      (node (ref "IC2") (pin "21") (pinfunction "I2C2_SCL/USART3_TX/RM-TIM2_CH3/PB10_21") (pintype "bidirectional"))
    )
    (net (code "58") (name "unconnected-(IC2D-I2C2_SDA{slash}USART3_RX{slash}RM-TIM2_CH4{slash}PB11-Pad22)") (class "Default")
      (node (ref "IC2") (pin "22") (pinfunction "I2C2_SDA/USART3_RX/RM-TIM2_CH4/PB11_22") (pintype "bidirectional"))
    )
    (net (code "59") (name "unconnected-(IC2D-I2C2_SMBA{slash}USART3_CK{slash}TIM1_BKIN{slash}SPI2_NSS{slash}PB12-Pad25)") (class "Default")
      (node (ref "IC2") (pin "25") (pinfunction "I2C2_SMBA/USART3_CK/TIM1_BKIN/SPI2_NSS/PB12_25") (pintype "bidirectional"))
    )
    (net (code "60") (name "unconnected-(IC2D-SPI2_MOSI{slash}TIM1_CH3N{slash}PB15-Pad28)") (class "Default")
      (node (ref "IC2") (pin "28") (pinfunction "SPI2_MOSI/TIM1_CH3N/PB15_28") (pintype "bidirectional"))
    )
    (net (code "61") (name "unconnected-(IC2D-USART3_CTS{slash}TIM1_CH1N{slash}SPI2_SCK{slash}PB13-Pad26)") (class "Default")
      (node (ref "IC2") (pin "26") (pinfunction "USART3_CTS/TIM1_CH1N/SPI2_SCK/PB13_26") (pintype "bidirectional"))
    )
    (net (code "62") (name "unconnected-(IC2D-USART3_RTS{slash}TIM1_CH2N{slash}SPI2_MISO{slash}PB14-Pad27)") (class "Default")
      (node (ref "IC2") (pin "27") (pinfunction "USART3_RTS/TIM1_CH2N/SPI2_MISO/PB14_27") (pintype "bidirectional"))
    )
    (net (code "63") (name "unconnected-(IC2E-ADC12_IN8{slash}TIM3_CH3{slash}RM-TIM1_CH2N{slash}PB0-Pad18)") (class "Default")
      (node (ref "IC2") (pin "18") (pinfunction "ADC12_IN8/TIM3_CH3/RM-TIM1_CH2N/PB0_18") (pintype "bidirectional"))
    )
    (net (code "64") (name "unconnected-(IC2E-ADC12_IN9{slash}TIM3_CH4{slash}RM-TIM1_CH3N{slash}PB1-Pad19)") (class "Default")
      (node (ref "IC2") (pin "19") (pinfunction "ADC12_IN9/TIM3_CH4/RM-TIM1_CH3N/PB1_19") (pintype "bidirectional"))
    )
    (net (code "65") (name "unconnected-(IC2E-BOOT1{slash}PB2-Pad20)") (class "Default")
      (node (ref "IC2") (pin "20") (pinfunction "BOOT1/PB2_20") (pintype "bidirectional"))
    )
    (net (code "66") (name "unconnected-(IC2E-I2C1_SCL{slash}TIM4_CH1{slash}RM-USART1_TX{slash}PB6-Pad42)") (class "Default")
      (node (ref "IC2") (pin "42") (pinfunction "I2C1_SCL/TIM4_CH1/RM-USART1_TX/PB6_42") (pintype "bidirectional"))
    )
    (net (code "67") (name "unconnected-(IC2E-I2C1_SMBAI{slash}RM-TIM3_CH2{slash}RM-SPI1_MOSI{slash}PB5-Pad41)") (class "Default")
      (node (ref "IC2") (pin "41") (pinfunction "I2C1_SMBAI/RM-TIM3_CH2/RM-SPI1_MOSI/PB5_41") (pintype "bidirectional"))
    )
    (net (code "68") (name "unconnected-(IC2E-RM-TIM2_CH2{slash}RM-SPI1_SCK{slash}PB3-Pad39)") (class "Default")
      (node (ref "IC2") (pin "39") (pinfunction "RM-TIM2_CH2/RM-SPI1_SCK/PB3_39") (pintype "bidirectional"))
    )
    (net (code "69") (name "unconnected-(IC2E-RM-TIM3_CH1{slash}RM-SPI1_MISO{slash}JUNTRAST{slash}PB4-Pad40)") (class "Default")
      (node (ref "IC2") (pin "40") (pinfunction "RM-TIM3_CH1/RM-SPI1_MISO/JUNTRAST/PB4_40") (pintype "bidirectional"))
    )
    (net (code "70") (name "unconnected-(IC2F-PC13{slash}TAMPER-RTC-Pad2)") (class "Default")
      (node (ref "IC2") (pin "2") (pinfunction "PC13/TAMPER-RTC_2") (pintype "bidirectional"))
    )
    (net (code "71") (name "unconnected-(IC2F-PC14{slash}OSC32_IN-Pad3)") (class "Default")
      (node (ref "IC2") (pin "3") (pinfunction "PC14/OSC32_IN_3") (pintype "bidirectional"))
    )
    (net (code "72") (name "unconnected-(IC2F-PC15{slash}OSC32_OUT-Pad4)") (class "Default")
      (node (ref "IC2") (pin "4") (pinfunction "PC15/OSC32_OUT_4") (pintype "bidirectional"))
    )
    (net (code "73") (name "unconnected-(IC5-NC-Pad5)") (class "Default")
      (node (ref "IC5") (pin "5") (pinfunction "NC_5") (pintype "no_connect"))
    )
    (net (code "74") (name "unconnected-(IC7-NC-Pad5)") (class "Default")
      (node (ref "IC7") (pin "5") (pinfunction "NC_5") (pintype "no_connect"))
    )
    (net (code "75") (name "unconnected-(JP1-Pad5)") (class "Default")
      (node (ref "JP1") (pin "5") (pinfunction "5_5") (pintype "passive"))
    )
    (net (code "76") (name "unconnected-(JP2-Pad5)") (class "Default")
      (node (ref "JP2") (pin "5") (pinfunction "5_5") (pintype "passive"))
    )
    (net (code "77") (name "unconnected-(SWD-Pad4)") (class "Default")
      (node (ref "SWD") (pin "4") (pinfunction "4_4") (pintype "passive"))
    )
  )
)
